# Balancing.net
KiCad netlist of a schematic drawn in Altium Designer
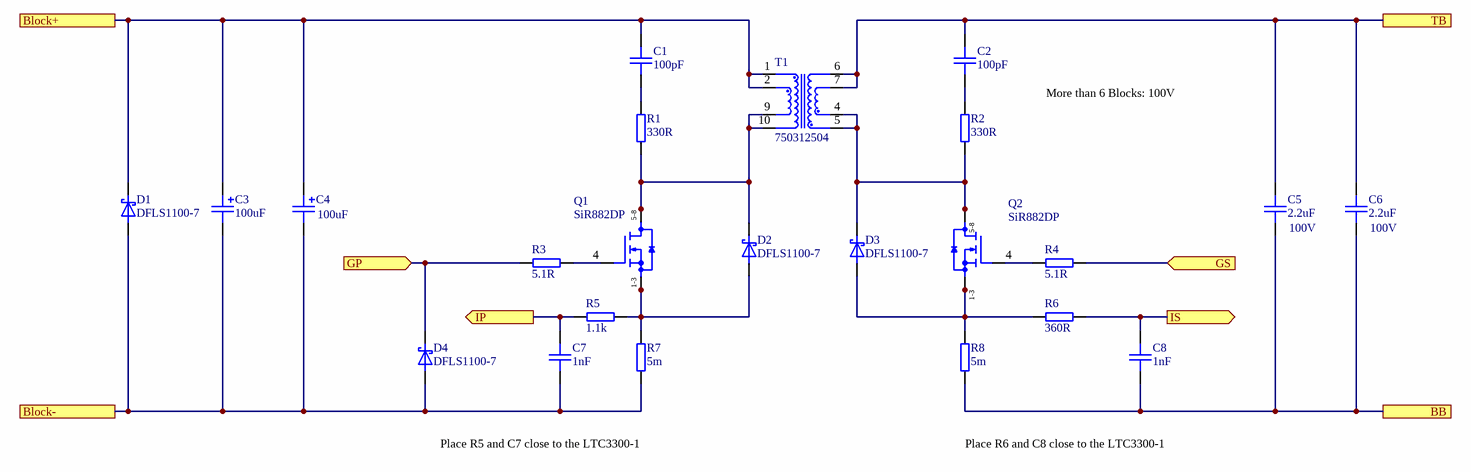
[diagram p0: Balancing.SchDoc]

(export (version "E")
  (design (tool "Eeschema 10.0.6"))
  (components
    (comp (ref "C1")
      (value "100pF")
      (footprint "CAP 0603")
      (fields (field (name "TOLERANCE") "5%") (field (name "VOLTAGE") "50V"))
      (libsource (lib "SVNDatabase") (part "Capacitor"))
    )
    (comp (ref "C2")
      (value "100pF")
      (footprint "CAP 0603")
      (fields (field (name "TOLERANCE") "5%") (field (name "VOLTAGE") "50V"))
      (libsource (lib "SVNDatabase") (part "Capacitor"))
    )
    (comp (ref "C3")
      (value "100uF")
      (footprint "KO-CAP T591D")
      (fields (field (name "TOLERANCE") "20%") (field (name "VOLTAGE") "16V"))
      (libsource (lib "SVNDatabase") (part "Polarized Capacitor"))
    )
    (comp (ref "C4")
      (value "100uF")
      (footprint "KO-CAP T591D")
      (fields (field (name "TOLERANCE") "20%") (field (name "VOLTAGE") "16V"))
      (libsource (lib "SVNDatabase") (part "Polarized Capacitor"))
    )
    (comp (ref "C5")
      (value "2.2uF")
      (footprint "CAP 1210")
      (fields (field (name "TOLERANCE") "10%") (field (name "VOLTAGE") "100V"))
      (libsource (lib "SVNDatabase") (part "Capacitor"))
    )
    (comp (ref "C6")
      (value "2.2uF")
      (footprint "CAP 1210")
      (fields (field (name "TOLERANCE") "10%") (field (name "VOLTAGE") "100V"))
      (libsource (lib "SVNDatabase") (part "Capacitor"))
    )
    (comp (ref "C7")
      (value "1nF")
      (footprint "CAP 0603")
      (fields (field (name "TOLERANCE") "10%") (field (name "VOLTAGE") "50V"))
      (libsource (lib "SVNDatabase") (part "Capacitor"))
    )
    (comp (ref "C8")
      (value "1nF")
      (footprint "CAP 0603")
      (fields (field (name "TOLERANCE") "10%") (field (name "VOLTAGE") "50V"))
      (libsource (lib "SVNDatabase") (part "Capacitor"))
    )
    (comp (ref "D1")
      (value "DFLS1100-7")
      (footprint "PowerDI-123")
      (libsource (lib "SVNDatabase") (part "Schottky Diode"))
    )
    (comp (ref "D2")
      (value "DFLS1100-7")
      (footprint "PowerDI-123")
      (libsource (lib "SVNDatabase") (part "Schottky Diode"))
    )
    (comp (ref "D3")
      (value "DFLS1100-7")
      (footprint "PowerDI-123")
      (libsource (lib "SVNDatabase") (part "Schottky Diode"))
    )
    (comp (ref "D4")
      (value "DFLS1100-7")
      (footprint "PowerDI-123")
      (libsource (lib "SVNDatabase") (part "Schottky Diode"))
    )
    (comp (ref "Q1")
      (value "SiR882DP")
      (footprint "PowerPAK SO-8 Single")
      (libsource (lib "SVNDatabase") (part "MOSFET N-Type PowerPAK SO-8"))
    )
    (comp (ref "Q2")
      (value "SiR882DP")
      (footprint "PowerPAK SO-8 Single")
      (libsource (lib "SVNDatabase") (part "MOSFET N-Type PowerPAK SO-8"))
    )
    (comp (ref "R1")
      (value "330R")
      (footprint "0603")
      (fields (field (name "TOLERANCE") "1%"))
      (libsource (lib "SVNDatabase") (part "R"))
    )
    (comp (ref "R2")
      (value "330R")
      (footprint "0603")
      (fields (field (name "TOLERANCE") "1%"))
      (libsource (lib "SVNDatabase") (part "R"))
    )
    (comp (ref "R3")
      (value "5.1R")
      (footprint "0603")
      (fields (field (name "TOLERANCE") "1%"))
      (libsource (lib "SVNDatabase") (part "R"))
    )
    (comp (ref "R4")
      (value "5.1R")
      (footprint "0603")
      (fields (field (name "TOLERANCE") "1%"))
      (libsource (lib "SVNDatabase") (part "R"))
    )
    (comp (ref "R5")
      (value "1.1k")
      (footprint "0603")
      (fields (field (name "TOLERANCE") "1%"))
      (libsource (lib "SVNDatabase") (part "R"))
    )
    (comp (ref "R6")
      (value "360R")
      (footprint "0603")
      (fields (field (name "TOLERANCE") "1%"))
      (libsource (lib "SVNDatabase") (part "R"))
    )
    (comp (ref "R7") (value "5m") (footprint "WSL1206 2m to 5m9") (libsource (lib "SVNDatabase") (part "R")))
    (comp (ref "R8") (value "5m") (footprint "WSL1206 2m to 5m9") (libsource (lib "SVNDatabase") (part "R")))
    (comp (ref "T1")
      (value "750312504")
      (footprint "750312504")
      (description "Flyback Transformer")
      (fields (field (name "TOLERANCE") "10%"))
      (libsource (lib "SVNDatabase") (part "750312504"))
    )
  )
  (nets
    (net (code "1") (name "/BB") (class "Default")
      (node (ref "C5") (pin "1") (pinfunction "1_1") (pintype "passive"))
      (node (ref "C6") (pin "1") (pinfunction "1_1") (pintype "passive"))
      (node (ref "C8") (pin "1") (pinfunction "1_1") (pintype "passive"))
      (node (ref "R8") (pin "1") (pinfunction "1_1") (pintype "passive"))
    )
    (net (code "2") (name "/Block+") (class "Default")
      (node (ref "C1") (pin "2") (pinfunction "2_2") (pintype "passive"))
      (node (ref "C3") (pin "1") (pinfunction "1_1") (pintype "passive"))
      (node (ref "C4") (pin "1") (pinfunction "1_1") (pintype "passive"))
      (node (ref "D1") (pin "2") (pinfunction "2_2") (pintype "passive"))
      (node (ref "T1") (pin "1") (pinfunction "1_1") (pintype "passive"))
      (node (ref "T1") (pin "2") (pinfunction "2_2") (pintype "passive"))
    )
    (net (code "3") (name "/Block-") (class "Default")
      (node (ref "C3") (pin "2") (pinfunction "2_2") (pintype "passive"))
      (node (ref "C4") (pin "2") (pinfunction "2_2") (pintype "passive"))
      (node (ref "C7") (pin "1") (pinfunction "1_1") (pintype "passive"))
      (node (ref "D1") (pin "1") (pinfunction "1_1") (pintype "passive"))
      (node (ref "D4") (pin "1") (pinfunction "1_1") (pintype "passive"))
      (node (ref "R7") (pin "1") (pinfunction "1_1") (pintype "passive"))
    )
    (net (code "4") (name "/GP") (class "Default")
      (node (ref "D4") (pin "2") (pinfunction "2_2") (pintype "passive"))
      (node (ref "R3") (pin "1") (pinfunction "1_1") (pintype "passive"))
    )
    (net (code "5") (name "/GS") (class "Default")
      (node (ref "R4") (pin "2") (pinfunction "2_2") (pintype "passive"))
    )
    (net (code "6") (name "/IP") (class "Default")
      (node (ref "C7") (pin "2") (pinfunction "2_2") (pintype "passive"))
      (node (ref "R5") (pin "1") (pinfunction "1_1") (pintype "passive"))
    )
    (net (code "7") (name "/IS") (class "Default")
      (node (ref "C8") (pin "2") (pinfunction "2_2") (pintype "passive"))
      (node (ref "R6") (pin "2") (pinfunction "2_2") (pintype "passive"))
    )
    (net (code "8") (name "/TB") (class "Default")
      (node (ref "C2") (pin "2") (pinfunction "2_2") (pintype "passive"))
      (node (ref "C5") (pin "2") (pinfunction "2_2") (pintype "passive"))
      (node (ref "C6") (pin "2") (pinfunction "2_2") (pintype "passive"))
      (node (ref "T1") (pin "6") (pinfunction "6_6") (pintype "passive"))
      (node (ref "T1") (pin "7") (pinfunction "7_7") (pintype "passive"))
    )
    (net (code "9") (name "Net-(C1-Pad1)") (class "Default")
      (node (ref "C1") (pin "1") (pinfunction "1_1") (pintype "passive"))
      (node (ref "R1") (pin "2") (pinfunction "2_2") (pintype "passive"))
    )
    (net (code "10") (name "Net-(C2-Pad1)") (class "Default")
      (node (ref "C2") (pin "1") (pinfunction "1_1") (pintype "passive"))
      (node (ref "R2") (pin "2") (pinfunction "2_2") (pintype "passive"))
    )
    (net (code "11") (name "Net-(D2-Pad1)") (class "Default")
      (node (ref "D2") (pin "1") (pinfunction "1_1") (pintype "passive"))
      (node (ref "Q1") (pin "1") (pinfunction "S_1") (pintype "passive"))
      (node (ref "Q1") (pin "2") (pinfunction "S_2") (pintype "passive"))
      (node (ref "Q1") (pin "3") (pinfunction "S_3") (pintype "passive"))
      (node (ref "R5") (pin "2") (pinfunction "2_2") (pintype "passive"))
      (node (ref "R7") (pin "2") (pinfunction "2_2") (pintype "passive"))
    )
    (net (code "12") (name "Net-(D2-Pad2)") (class "Default")
      (node (ref "D2") (pin "2") (pinfunction "2_2") (pintype "passive"))
      (node (ref "Q1") (pin "5") (pinfunction "D_5") (pintype "passive"))
      (node (ref "Q1") (pin "6") (pinfunction "D_6") (pintype "passive"))
      (node (ref "Q1") (pin "7") (pinfunction "D_7") (pintype "passive"))
      (node (ref "Q1") (pin "8") (pinfunction "D_8") (pintype "passive"))
      (node (ref "R1") (pin "1") (pinfunction "1_1") (pintype "passive"))
      (node (ref "T1") (pin "10") (pinfunction "10_10") (pintype "passive"))
      (node (ref "T1") (pin "9") (pinfunction "9_9") (pintype "passive"))
    )
    (net (code "13") (name "Net-(D3-Pad1)") (class "Default")
      (node (ref "D3") (pin "1") (pinfunction "1_1") (pintype "passive"))
      (node (ref "Q2") (pin "1") (pinfunction "S_1") (pintype "passive"))
      (node (ref "Q2") (pin "2") (pinfunction "S_2") (pintype "passive"))
      (node (ref "Q2") (pin "3") (pinfunction "S_3") (pintype "passive"))
      (node (ref "R6") (pin "1") (pinfunction "1_1") (pintype "passive"))
      (node (ref "R8") (pin "2") (pinfunction "2_2") (pintype "passive"))
    )
    (net (code "14") (name "Net-(D3-Pad2)") (class "Default")
      (node (ref "D3") (pin "2") (pinfunction "2_2") (pintype "passive"))
      (node (ref "Q2") (pin "5") (pinfunction "D_5") (pintype "passive"))
      (node (ref "Q2") (pin "6") (pinfunction "D_6") (pintype "passive"))
      (node (ref "Q2") (pin "7") (pinfunction "D_7") (pintype "passive"))
      (node (ref "Q2") (pin "8") (pinfunction "D_8") (pintype "passive"))
      (node (ref "R2") (pin "1") (pinfunction "1_1") (pintype "passive"))
      (node (ref "T1") (pin "4") (pinfunction "4_4") (pintype "passive"))
      (node (ref "T1") (pin "5") (pinfunction "5_5") (pintype "passive"))
    )
    (net (code "15") (name "Net-(Q1-G)") (class "Default")
      (node (ref "Q1") (pin "4") (pinfunction "G_4") (pintype "passive"))
      (node (ref "R3") (pin "2") (pinfunction "2_2") (pintype "passive"))
    )
    (net (code "16") (name "Net-(Q2-G)") (class "Default")
      (node (ref "Q2") (pin "4") (pinfunction "G_4") (pintype "passive"))
      (node (ref "R4") (pin "1") (pinfunction "1_1") (pintype "passive"))
    )
  )
)
